# Vaus_Arkanoid_paddle.net
KiCad netlist of a schematic drawn in EAGLE
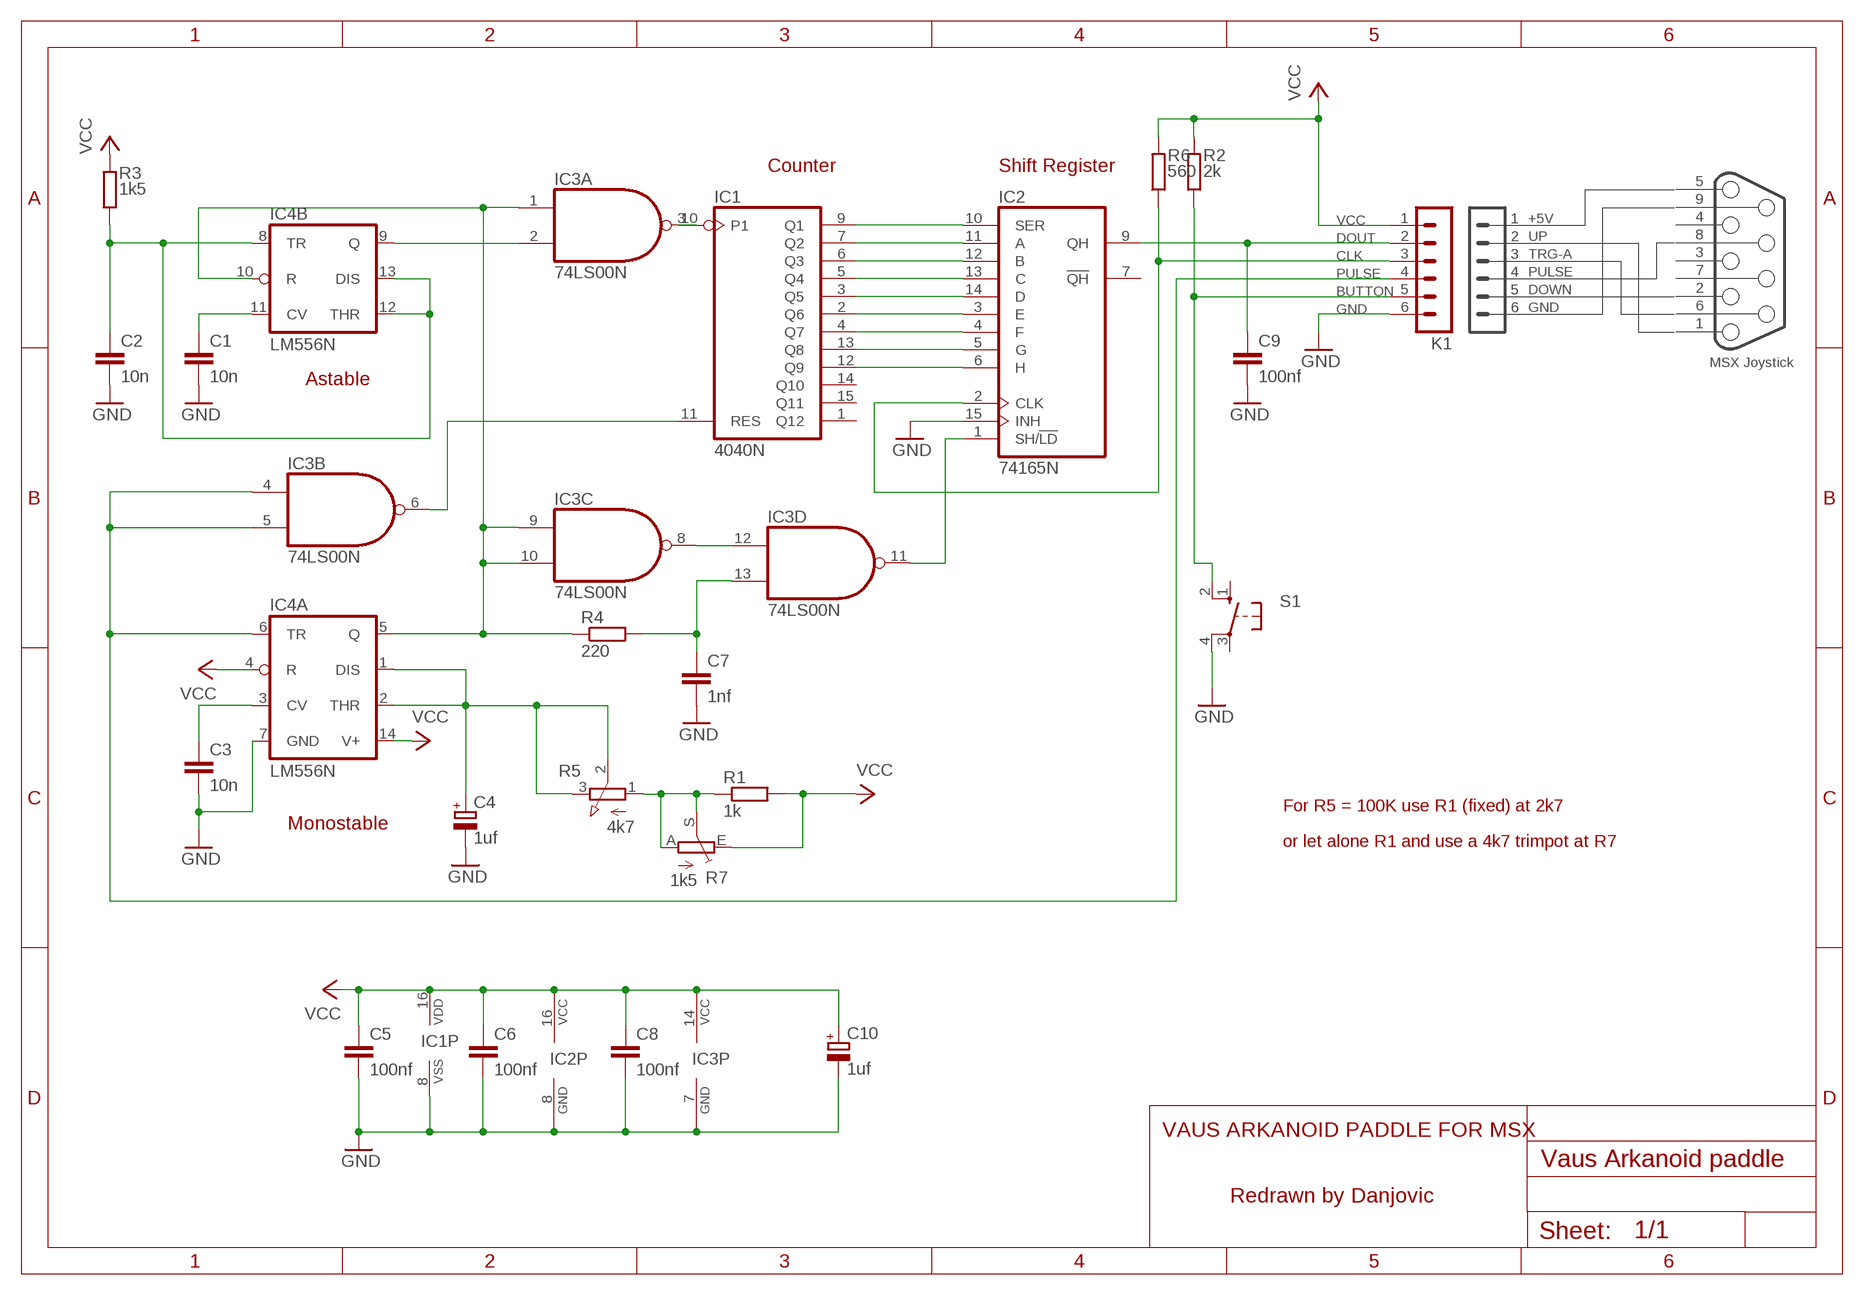
[diagram p0: schematic, sheet 1]

(export (version "E")
  (design (tool "Eeschema 10.0.6"))
  (components
    (comp (ref "C1")
      (value "10n")
      (footprint "eagle-import:C050-024X044")
      (libsource (lib "eagle-import") (part "C-EU050-024X044"))
    )
    (comp (ref "C2")
      (value "10n")
      (footprint "eagle-import:C050-024X044")
      (libsource (lib "eagle-import") (part "C-EU050-024X044"))
    )
    (comp (ref "C3")
      (value "10n")
      (footprint "eagle-import:C050-024X044")
      (libsource (lib "eagle-import") (part "C-EU050-024X044"))
    )
    (comp (ref "C4")
      (value "1uf")
      (footprint "eagle-import:E2-4")
      (libsource (lib "eagle-import") (part "CPOL-EUE2-4"))
    )
    (comp (ref "C5")
      (value "100nf")
      (footprint "eagle-import:C050-024X044")
      (libsource (lib "eagle-import") (part "C-EU050-024X044"))
    )
    (comp (ref "C6")
      (value "100nf")
      (footprint "eagle-import:C050-024X044")
      (libsource (lib "eagle-import") (part "C-EU050-024X044"))
    )
    (comp (ref "C7")
      (value "1nf")
      (footprint "eagle-import:C050-024X044")
      (libsource (lib "eagle-import") (part "C-EU050-024X044"))
    )
    (comp (ref "C8")
      (value "100nf")
      (footprint "eagle-import:C050-024X044")
      (libsource (lib "eagle-import") (part "C-EU050-024X044"))
    )
    (comp (ref "C9")
      (value "100nf")
      (footprint "eagle-import:C050-024X044")
      (libsource (lib "eagle-import") (part "C-EU050-024X044"))
    )
    (comp (ref "C10")
      (value "1uf")
      (footprint "eagle-import:E2-4")
      (libsource (lib "eagle-import") (part "CPOL-EUE2-4"))
    )
    (comp (ref "IC1")
      (value "4040N")
      (footprint "eagle-import:DIL16")
      (libsource (lib "eagle-import") (part "4040N"))
    )
    (comp (ref "IC2")
      (value "74165N")
      (footprint "eagle-import:DIL16")
      (libsource (lib "eagle-import") (part "74165N"))
    )
    (comp (ref "IC3")
      (value "74LS00N")
      (footprint "eagle-import:DIL14")
      (libsource (lib "eagle-import") (part "7400NLS"))
    )
    (comp (ref "IC4")
      (value "LM556N")
      (footprint "eagle-import:DIL14")
      (libsource (lib "eagle-import") (part "556NLM"))
    )
    (comp (ref "K1")
      (value "MA06-1")
      (footprint "eagle-import:MA06-1")
      (libsource (lib "eagle-import") (part "MA06-1"))
    )
    (comp (ref "R1")
      (value "1k")
      (footprint "eagle-import:0207_7")
      (libsource (lib "eagle-import") (part "R-EU_0207/7"))
    )
    (comp (ref "R2")
      (value "2k")
      (footprint "eagle-import:0207_7")
      (libsource (lib "eagle-import") (part "R-EU_0207/7"))
    )
    (comp (ref "R3")
      (value "1k5")
      (footprint "eagle-import:0207_7")
      (libsource (lib "eagle-import") (part "R-EU_0207/7"))
    )
    (comp (ref "R4")
      (value "220")
      (footprint "eagle-import:0207_7")
      (libsource (lib "eagle-import") (part "R-EU_0207/7"))
    )
    (comp (ref "R5")
      (value "4k7")
      (footprint "eagle-import:3RP_1610N_THRU")
      (libsource (lib "eagle-import") (part "3RP/1610NTHRU"))
    )
    (comp (ref "R6")
      (value "560")
      (footprint "eagle-import:0207_7")
      (libsource (lib "eagle-import") (part "R-EU_0207/7"))
    )
    (comp (ref "R7")
      (value "1k5")
      (footprint "eagle-import:CT6")
      (libsource (lib "eagle-import") (part "TRIM_EU-CT6"))
    )
    (comp (ref "S1")
      (value "40-XX")
      (footprint "eagle-import:B3F-40XX")
      (fields (field (name "MF") "OMRON COMPONENTS USA") (field (name "MPN") "B3F-4000"))
      (libsource (lib "eagle-import") (part "40-XX"))
    )
  )
  (nets
    (net (code "1") (name "/BUTTON") (class "Default")
      (node (ref "K1") (pin "5") (pinfunction "5_5") (pintype "passive"))
      (node (ref "R2") (pin "1") (pinfunction "1_1") (pintype "passive"))
      (node (ref "S1") (pin "2") (pinfunction "S1_2") (pintype "passive"))
    )
    (net (code "2") (name "/CLK") (class "Default")
      (node (ref "IC2") (pin "2") (pinfunction "CLK_2") (pintype "input"))
      (node (ref "K1") (pin "3") (pinfunction "3_3") (pintype "passive"))
      (node (ref "R6") (pin "1") (pinfunction "1_1") (pintype "passive"))
    )
    (net (code "3") (name "/DOUT") (class "Default")
      (node (ref "C9") (pin "1") (pinfunction "1_1") (pintype "passive"))
      (node (ref "IC2") (pin "9") (pinfunction "QH_9") (pintype "output"))
      (node (ref "K1") (pin "2") (pinfunction "2_2") (pintype "passive"))
    )
    (net (code "4") (name "/PULSE") (class "Default")
      (node (ref "IC3") (pin "4") (pinfunction "I0_4") (pintype "input"))
      (node (ref "IC3") (pin "5") (pinfunction "I1_5") (pintype "input"))
      (node (ref "IC4") (pin "6") (pinfunction "TR_6") (pintype "input"))
      (node (ref "K1") (pin "4") (pinfunction "4_4") (pintype "passive"))
    )
    (net (code "5") (name "GND") (class "Default")
      (node (ref "C1") (pin "2") (pinfunction "2_2") (pintype "passive"))
      (node (ref "C10") (pin "-") (pinfunction "-_-") (pintype "passive"))
      (node (ref "C2") (pin "2") (pinfunction "2_2") (pintype "passive"))
      (node (ref "C3") (pin "2") (pinfunction "2_2") (pintype "passive"))
      (node (ref "C4") (pin "-") (pinfunction "-_-") (pintype "passive"))
      (node (ref "C5") (pin "2") (pinfunction "2_2") (pintype "passive"))
      (node (ref "C6") (pin "2") (pinfunction "2_2") (pintype "passive"))
      (node (ref "C7") (pin "2") (pinfunction "2_2") (pintype "passive"))
      (node (ref "C8") (pin "2") (pinfunction "2_2") (pintype "passive"))
      (node (ref "C9") (pin "2") (pinfunction "2_2") (pintype "passive"))
      (node (ref "IC1") (pin "8") (pinfunction "VSS_8") (pintype "power_in"))
      (node (ref "IC2") (pin "15") (pinfunction "INH_15") (pintype "input"))
      (node (ref "IC2") (pin "8") (pinfunction "GND_8") (pintype "power_in"))
      (node (ref "IC3") (pin "7") (pinfunction "GND_7") (pintype "power_in"))
      (node (ref "IC4") (pin "7") (pinfunction "GND_7") (pintype "power_in"))
      (node (ref "K1") (pin "6") (pinfunction "6_6") (pintype "passive"))
      (node (ref "S1") (pin "4") (pinfunction "P1_4") (pintype "passive"))
    )
    (net (code "6") (name "Net-(IC1A-P1)") (class "Default")
      (node (ref "IC1") (pin "10") (pinfunction "P1_10") (pintype "input"))
      (node (ref "IC3") (pin "3") (pinfunction "O_3") (pintype "output"))
    )
    (net (code "7") (name "Net-(IC1A-Q1)") (class "Default")
      (node (ref "IC1") (pin "9") (pinfunction "Q1_9") (pintype "output"))
      (node (ref "IC2") (pin "10") (pinfunction "SER_10") (pintype "input"))
    )
    (net (code "8") (name "Net-(IC1A-Q2)") (class "Default")
      (node (ref "IC1") (pin "7") (pinfunction "Q2_7") (pintype "output"))
      (node (ref "IC2") (pin "11") (pinfunction "A_11") (pintype "input"))
    )
    (net (code "9") (name "Net-(IC1A-Q3)") (class "Default")
      (node (ref "IC1") (pin "6") (pinfunction "Q3_6") (pintype "output"))
      (node (ref "IC2") (pin "12") (pinfunction "B_12") (pintype "input"))
    )
    (net (code "10") (name "Net-(IC1A-Q4)") (class "Default")
      (node (ref "IC1") (pin "5") (pinfunction "Q4_5") (pintype "output"))
      (node (ref "IC2") (pin "13") (pinfunction "C_13") (pintype "input"))
    )
    (net (code "11") (name "Net-(IC1A-Q5)") (class "Default")
      (node (ref "IC1") (pin "3") (pinfunction "Q5_3") (pintype "output"))
      (node (ref "IC2") (pin "14") (pinfunction "D_14") (pintype "input"))
    )
    (net (code "12") (name "Net-(IC1A-Q6)") (class "Default")
      (node (ref "IC1") (pin "2") (pinfunction "Q6_2") (pintype "output"))
      (node (ref "IC2") (pin "3") (pinfunction "E_3") (pintype "input"))
    )
    (net (code "13") (name "Net-(IC1A-Q7)") (class "Default")
      (node (ref "IC1") (pin "4") (pinfunction "Q7_4") (pintype "output"))
      (node (ref "IC2") (pin "4") (pinfunction "F_4") (pintype "input"))
    )
    (net (code "14") (name "Net-(IC1A-Q8)") (class "Default")
      (node (ref "IC1") (pin "13") (pinfunction "Q8_13") (pintype "output"))
      (node (ref "IC2") (pin "5") (pinfunction "G_5") (pintype "input"))
    )
    (net (code "15") (name "Net-(IC1A-Q9)") (class "Default")
      (node (ref "IC1") (pin "12") (pinfunction "Q9_12") (pintype "output"))
      (node (ref "IC2") (pin "6") (pinfunction "H_6") (pintype "input"))
    )
    (net (code "16") (name "Net-(IC1A-RES)") (class "Default")
      (node (ref "IC1") (pin "11") (pinfunction "RES_11") (pintype "input"))
      (node (ref "IC3") (pin "6") (pinfunction "O_6") (pintype "output"))
    )
    (net (code "17") (name "Net-(IC2A-SH{slash}~{LD})") (class "Default")
      (node (ref "IC2") (pin "1") (pinfunction "SH/~{LD}_1") (pintype "input"))
      (node (ref "IC3") (pin "11") (pinfunction "O_11") (pintype "output"))
    )
    (net (code "18") (name "Net-(IC3A-I0)") (class "Default")
      (node (ref "IC3") (pin "1") (pinfunction "I0_1") (pintype "input"))
      (node (ref "IC3") (pin "10") (pinfunction "I1_10") (pintype "input"))
      (node (ref "IC3") (pin "9") (pinfunction "I0_9") (pintype "input"))
      (node (ref "IC4") (pin "10") (pinfunction "R_10") (pintype "input"))
      (node (ref "IC4") (pin "5") (pinfunction "Q_5") (pintype "output"))
      (node (ref "R4") (pin "1") (pinfunction "1_1") (pintype "passive"))
    )
    (net (code "19") (name "Net-(IC3A-I1)") (class "Default")
      (node (ref "IC3") (pin "2") (pinfunction "I1_2") (pintype "input"))
      (node (ref "IC4") (pin "9") (pinfunction "Q_9") (pintype "output"))
    )
    (net (code "20") (name "Net-(IC3C-O)") (class "Default")
      (node (ref "IC3") (pin "12") (pinfunction "I0_12") (pintype "input"))
      (node (ref "IC3") (pin "8") (pinfunction "O_8") (pintype "output"))
    )
    (net (code "21") (name "Net-(IC3D-I1)") (class "Default")
      (node (ref "C7") (pin "1") (pinfunction "1_1") (pintype "passive"))
      (node (ref "IC3") (pin "13") (pinfunction "I1_13") (pintype "input"))
      (node (ref "R4") (pin "2") (pinfunction "2_2") (pintype "passive"))
    )
    (net (code "22") (name "Net-(IC4A-CV)") (class "Default")
      (node (ref "C3") (pin "1") (pinfunction "1_1") (pintype "passive"))
      (node (ref "IC4") (pin "3") (pinfunction "CV_3") (pintype "input"))
    )
    (net (code "23") (name "Net-(IC4A-DIS)") (class "Default")
      (node (ref "C4") (pin "+") (pinfunction "+_+") (pintype "passive"))
      (node (ref "IC4") (pin "1") (pinfunction "DIS_1") (pintype "input"))
      (node (ref "IC4") (pin "2") (pinfunction "THR_2") (pintype "input"))
      (node (ref "R5") (pin "2") (pinfunction "S_2") (pintype "passive"))
      (node (ref "R5") (pin "3") (pinfunction "E_3") (pintype "passive"))
    )
    (net (code "24") (name "Net-(IC4B-CV)") (class "Default")
      (node (ref "C1") (pin "1") (pinfunction "1_1") (pintype "passive"))
      (node (ref "IC4") (pin "11") (pinfunction "CV_11") (pintype "input"))
    )
    (net (code "25") (name "Net-(IC4B-DIS)") (class "Default")
      (node (ref "C2") (pin "1") (pinfunction "1_1") (pintype "passive"))
      (node (ref "IC4") (pin "12") (pinfunction "THR_12") (pintype "input"))
      (node (ref "IC4") (pin "13") (pinfunction "DIS_13") (pintype "input"))
      (node (ref "IC4") (pin "8") (pinfunction "TR_8") (pintype "input"))
      (node (ref "R3") (pin "1") (pinfunction "1_1") (pintype "passive"))
    )
    (net (code "26") (name "Net-(R5-A)") (class "Default")
      (node (ref "R1") (pin "1") (pinfunction "1_1") (pintype "passive"))
      (node (ref "R5") (pin "1") (pinfunction "A_1") (pintype "passive"))
      (node (ref "R7") (pin "A") (pinfunction "A_A") (pintype "passive"))
      (node (ref "R7") (pin "S") (pinfunction "S_S") (pintype "passive"))
    )
    (net (code "27") (name "VCC") (class "Default")
      (node (ref "C10") (pin "+") (pinfunction "+_+") (pintype "passive"))
      (node (ref "C5") (pin "1") (pinfunction "1_1") (pintype "passive"))
      (node (ref "C6") (pin "1") (pinfunction "1_1") (pintype "passive"))
      (node (ref "C8") (pin "1") (pinfunction "1_1") (pintype "passive"))
      (node (ref "IC1") (pin "16") (pinfunction "VDD_16") (pintype "power_in"))
      (node (ref "IC2") (pin "16") (pinfunction "VCC_16") (pintype "power_in"))
      (node (ref "IC3") (pin "14") (pinfunction "VCC_14") (pintype "power_in"))
      (node (ref "IC4") (pin "14") (pinfunction "V+_14") (pintype "power_in"))
      (node (ref "IC4") (pin "4") (pinfunction "R_4") (pintype "input"))
      (node (ref "K1") (pin "1") (pinfunction "1_1") (pintype "passive"))
      (node (ref "R1") (pin "2") (pinfunction "2_2") (pintype "passive"))
      (node (ref "R2") (pin "2") (pinfunction "2_2") (pintype "passive"))
      (node (ref "R3") (pin "2") (pinfunction "2_2") (pintype "passive"))
      (node (ref "R6") (pin "2") (pinfunction "2_2") (pintype "passive"))
      (node (ref "R7") (pin "E") (pinfunction "E_E") (pintype "passive"))
    )
    (net (code "28") (name "unconnected-(IC1A-Q10-Pad14)") (class "Default")
      (node (ref "IC1") (pin "14") (pinfunction "Q10_14") (pintype "output"))
    )
    (net (code "29") (name "unconnected-(IC1A-Q11-Pad15)") (class "Default")
      (node (ref "IC1") (pin "15") (pinfunction "Q11_15") (pintype "output"))
    )
    (net (code "30") (name "unconnected-(IC1A-Q12-Pad1)") (class "Default")
      (node (ref "IC1") (pin "1") (pinfunction "Q12_1") (pintype "output"))
    )
    (net (code "31") (name "unconnected-(IC2A-~{QH}-Pad7)") (class "Default")
      (node (ref "IC2") (pin "7") (pinfunction "~{QH}_7") (pintype "output"))
    )
    (net (code "32") (name "unconnected-(S1-P-Pad3)") (class "Default")
      (node (ref "S1") (pin "3") (pinfunction "P_3") (pintype "passive"))
    )
    (net (code "33") (name "unconnected-(S1-S-Pad1)") (class "Default")
      (node (ref "S1") (pin "1") (pinfunction "S_1") (pintype "passive"))
    )
  )
)
